# Connectors.net
KiCad netlist of a schematic drawn in Altium Designer
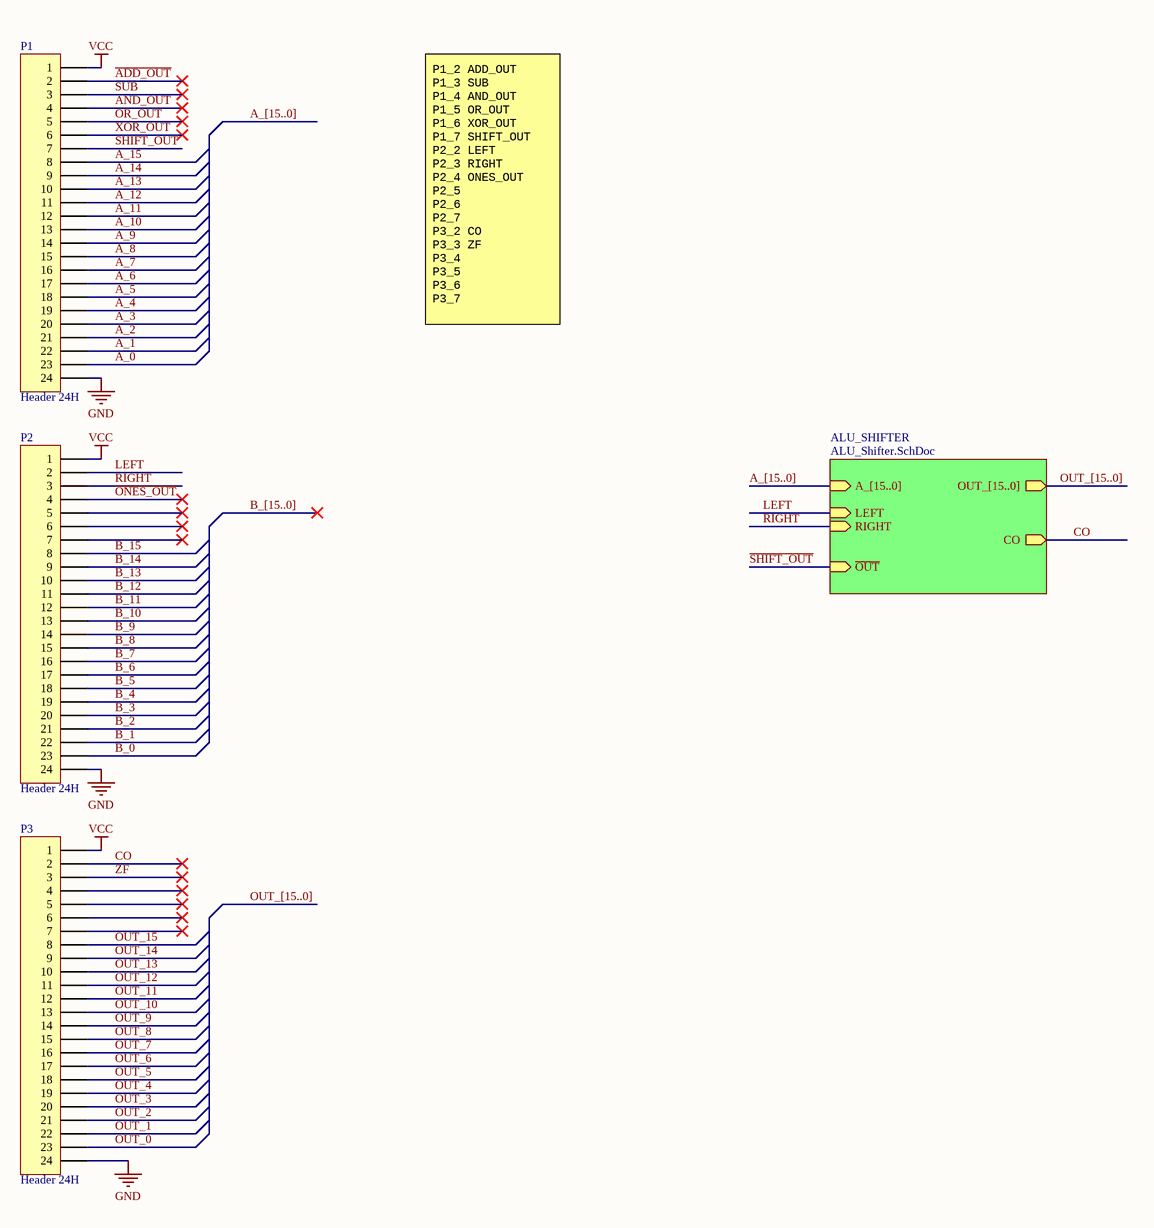
[diagram p0: Connectors.SchDoc]

(export (version "E")
  (design (tool "Eeschema 10.0.6"))
  (components
    (comp (ref "P1")
      (value "Header 24H")
      (footprint "HDR1X24H")
      (description "Header, 24-Pin, Right Angle")
      (fields (field (name "PUBLISHER") "Altium Limited"))
      (libsource (lib "Miscellaneous Connectors") (part "Header 24H"))
    )
    (comp (ref "P2")
      (value "Header 24H")
      (footprint "HDR1X24H")
      (description "Header, 24-Pin, Right Angle")
      (fields (field (name "PUBLISHER") "Altium Limited"))
      (libsource (lib "Miscellaneous Connectors") (part "Header 24H"))
    )
    (comp (ref "P3")
      (value "Header 24H")
      (footprint "HDR1X24H")
      (description "Header, 24-Pin, Right Angle")
      (fields (field (name "PUBLISHER") "Altium Limited"))
      (libsource (lib "Miscellaneous Connectors") (part "Header 24H"))
    )
  )
  (nets
    (net (code "1") (name "/A_0") (class "Default")
      (node (ref "P1") (pin "23") (pinfunction "23_23") (pintype "passive"))
    )
    (net (code "2") (name "/A_1") (class "Default")
      (node (ref "P1") (pin "22") (pinfunction "22_22") (pintype "passive"))
    )
    (net (code "3") (name "/A_2") (class "Default")
      (node (ref "P1") (pin "21") (pinfunction "21_21") (pintype "passive"))
    )
    (net (code "4") (name "/A_3") (class "Default")
      (node (ref "P1") (pin "20") (pinfunction "20_20") (pintype "passive"))
    )
    (net (code "5") (name "/A_4") (class "Default")
      (node (ref "P1") (pin "19") (pinfunction "19_19") (pintype "passive"))
    )
    (net (code "6") (name "/A_5") (class "Default")
      (node (ref "P1") (pin "18") (pinfunction "18_18") (pintype "passive"))
    )
    (net (code "7") (name "/A_6") (class "Default")
      (node (ref "P1") (pin "17") (pinfunction "17_17") (pintype "passive"))
    )
    (net (code "8") (name "/A_7") (class "Default")
      (node (ref "P1") (pin "16") (pinfunction "16_16") (pintype "passive"))
    )
    (net (code "9") (name "/A_8") (class "Default")
      (node (ref "P1") (pin "15") (pinfunction "15_15") (pintype "passive"))
    )
    (net (code "10") (name "/A_9") (class "Default")
      (node (ref "P1") (pin "14") (pinfunction "14_14") (pintype "passive"))
    )
    (net (code "11") (name "/A_10") (class "Default")
      (node (ref "P1") (pin "13") (pinfunction "13_13") (pintype "passive"))
    )
    (net (code "12") (name "/A_11") (class "Default")
      (node (ref "P1") (pin "12") (pinfunction "12_12") (pintype "passive"))
    )
    (net (code "13") (name "/A_12") (class "Default")
      (node (ref "P1") (pin "11") (pinfunction "11_11") (pintype "passive"))
    )
    (net (code "14") (name "/A_13") (class "Default")
      (node (ref "P1") (pin "10") (pinfunction "10_10") (pintype "passive"))
    )
    (net (code "15") (name "/A_14") (class "Default")
      (node (ref "P1") (pin "9") (pinfunction "9_9") (pintype "passive"))
    )
    (net (code "16") (name "/A_15") (class "Default")
      (node (ref "P1") (pin "8") (pinfunction "8_8") (pintype "passive"))
    )
    (net (code "18") (name "/B_0") (class "Default")
      (node (ref "P2") (pin "23") (pinfunction "23_23") (pintype "passive"))
    )
    (net (code "19") (name "/B_1") (class "Default")
      (node (ref "P2") (pin "22") (pinfunction "22_22") (pintype "passive"))
    )
    (net (code "20") (name "/B_2") (class "Default")
      (node (ref "P2") (pin "21") (pinfunction "21_21") (pintype "passive"))
    )
    (net (code "21") (name "/B_3") (class "Default")
      (node (ref "P2") (pin "20") (pinfunction "20_20") (pintype "passive"))
    )
    (net (code "22") (name "/B_4") (class "Default")
      (node (ref "P2") (pin "19") (pinfunction "19_19") (pintype "passive"))
    )
    (net (code "23") (name "/B_5") (class "Default")
      (node (ref "P2") (pin "18") (pinfunction "18_18") (pintype "passive"))
    )
    (net (code "24") (name "/B_6") (class "Default")
      (node (ref "P2") (pin "17") (pinfunction "17_17") (pintype "passive"))
    )
    (net (code "25") (name "/B_7") (class "Default")
      (node (ref "P2") (pin "16") (pinfunction "16_16") (pintype "passive"))
    )
    (net (code "26") (name "/B_8") (class "Default")
      (node (ref "P2") (pin "15") (pinfunction "15_15") (pintype "passive"))
    )
    (net (code "27") (name "/B_9") (class "Default")
      (node (ref "P2") (pin "14") (pinfunction "14_14") (pintype "passive"))
    )
    (net (code "28") (name "/B_10") (class "Default")
      (node (ref "P2") (pin "13") (pinfunction "13_13") (pintype "passive"))
    )
    (net (code "29") (name "/B_11") (class "Default")
      (node (ref "P2") (pin "12") (pinfunction "12_12") (pintype "passive"))
    )
    (net (code "30") (name "/B_12") (class "Default")
      (node (ref "P2") (pin "11") (pinfunction "11_11") (pintype "passive"))
    )
    (net (code "31") (name "/B_13") (class "Default")
      (node (ref "P2") (pin "10") (pinfunction "10_10") (pintype "passive"))
    )
    (net (code "32") (name "/B_14") (class "Default")
      (node (ref "P2") (pin "9") (pinfunction "9_9") (pintype "passive"))
    )
    (net (code "33") (name "/B_15") (class "Default")
      (node (ref "P2") (pin "8") (pinfunction "8_8") (pintype "passive"))
    )
    (net (code "35") (name "/CO") (class "Default")
      (node (ref "P3") (pin "2") (pinfunction "2_2") (pintype "passive"))
    )
    (net (code "36") (name "/LEFT") (class "Default")
      (node (ref "P2") (pin "2") (pinfunction "2_2") (pintype "passive"))
    )
    (net (code "37") (name "/OUT_0") (class "Default")
      (node (ref "P3") (pin "23") (pinfunction "23_23") (pintype "passive"))
    )
    (net (code "38") (name "/OUT_1") (class "Default")
      (node (ref "P3") (pin "22") (pinfunction "22_22") (pintype "passive"))
    )
    (net (code "39") (name "/OUT_2") (class "Default")
      (node (ref "P3") (pin "21") (pinfunction "21_21") (pintype "passive"))
    )
    (net (code "40") (name "/OUT_3") (class "Default")
      (node (ref "P3") (pin "20") (pinfunction "20_20") (pintype "passive"))
    )
    (net (code "41") (name "/OUT_4") (class "Default")
      (node (ref "P3") (pin "19") (pinfunction "19_19") (pintype "passive"))
    )
    (net (code "42") (name "/OUT_5") (class "Default")
      (node (ref "P3") (pin "18") (pinfunction "18_18") (pintype "passive"))
    )
    (net (code "43") (name "/OUT_6") (class "Default")
      (node (ref "P3") (pin "17") (pinfunction "17_17") (pintype "passive"))
    )
    (net (code "44") (name "/OUT_7") (class "Default")
      (node (ref "P3") (pin "16") (pinfunction "16_16") (pintype "passive"))
    )
    (net (code "45") (name "/OUT_8") (class "Default")
      (node (ref "P3") (pin "15") (pinfunction "15_15") (pintype "passive"))
    )
    (net (code "46") (name "/OUT_9") (class "Default")
      (node (ref "P3") (pin "14") (pinfunction "14_14") (pintype "passive"))
    )
    (net (code "47") (name "/OUT_10") (class "Default")
      (node (ref "P3") (pin "13") (pinfunction "13_13") (pintype "passive"))
    )
    (net (code "48") (name "/OUT_11") (class "Default")
      (node (ref "P3") (pin "12") (pinfunction "12_12") (pintype "passive"))
    )
    (net (code "49") (name "/OUT_12") (class "Default")
      (node (ref "P3") (pin "11") (pinfunction "11_11") (pintype "passive"))
    )
    (net (code "50") (name "/OUT_13") (class "Default")
      (node (ref "P3") (pin "10") (pinfunction "10_10") (pintype "passive"))
    )
    (net (code "51") (name "/OUT_14") (class "Default")
      (node (ref "P3") (pin "9") (pinfunction "9_9") (pintype "passive"))
    )
    (net (code "52") (name "/OUT_15") (class "Default")
      (node (ref "P3") (pin "8") (pinfunction "8_8") (pintype "passive"))
    )
    (net (code "54") (name "/RIGHT") (class "Default")
      (node (ref "P2") (pin "3") (pinfunction "3_3") (pintype "passive"))
    )
    (net (code "55") (name "/SUB") (class "Default")
      (node (ref "P1") (pin "3") (pinfunction "3_3") (pintype "passive+no_connect"))
    )
    (net (code "56") (name "/~{ADD_OUT}") (class "Default")
      (node (ref "P1") (pin "2") (pinfunction "2_2") (pintype "passive+no_connect"))
    )
    (net (code "57") (name "/~{AND_OUT}") (class "Default")
      (node (ref "P1") (pin "4") (pinfunction "4_4") (pintype "passive+no_connect"))
    )
    (net (code "58") (name "/~{ONES_OUT}") (class "Default")
      (node (ref "P2") (pin "4") (pinfunction "4_4") (pintype "passive+no_connect"))
    )
    (net (code "59") (name "/~{OR_OUT}") (class "Default")
      (node (ref "P1") (pin "5") (pinfunction "5_5") (pintype "passive+no_connect"))
    )
    (net (code "60") (name "/~{SHIFT_OUT}") (class "Default")
      (node (ref "P1") (pin "7") (pinfunction "7_7") (pintype "passive"))
    )
    (net (code "61") (name "/~{XOR_OUT}") (class "Default")
      (node (ref "P1") (pin "6") (pinfunction "6_6") (pintype "passive+no_connect"))
    )
    (net (code "62") (name "/~{ZF}") (class "Default")
      (node (ref "P3") (pin "3") (pinfunction "3_3") (pintype "passive+no_connect"))
    )
    (net (code "63") (name "GND") (class "Default")
      (node (ref "P1") (pin "24") (pinfunction "24_24") (pintype "passive"))
      (node (ref "P2") (pin "24") (pinfunction "24_24") (pintype "passive"))
      (node (ref "P3") (pin "24") (pinfunction "24_24") (pintype "passive"))
    )
    (net (code "64") (name "VCC") (class "Default")
      (node (ref "P1") (pin "1") (pinfunction "1_1") (pintype "passive"))
      (node (ref "P2") (pin "1") (pinfunction "1_1") (pintype "passive"))
      (node (ref "P3") (pin "1") (pinfunction "1_1") (pintype "passive"))
    )
    (net (code "65") (name "unconnected-(P2-Pad5)") (class "Default")
      (node (ref "P2") (pin "5") (pinfunction "5_5") (pintype "passive+no_connect"))
    )
    (net (code "66") (name "unconnected-(P2-Pad6)") (class "Default")
      (node (ref "P2") (pin "6") (pinfunction "6_6") (pintype "passive+no_connect"))
    )
    (net (code "67") (name "unconnected-(P2-Pad7)") (class "Default")
      (node (ref "P2") (pin "7") (pinfunction "7_7") (pintype "passive+no_connect"))
    )
    (net (code "68") (name "unconnected-(P3-Pad4)") (class "Default")
      (node (ref "P3") (pin "4") (pinfunction "4_4") (pintype "passive+no_connect"))
    )
    (net (code "69") (name "unconnected-(P3-Pad5)") (class "Default")
      (node (ref "P3") (pin "5") (pinfunction "5_5") (pintype "passive+no_connect"))
    )
    (net (code "70") (name "unconnected-(P3-Pad6)") (class "Default")
      (node (ref "P3") (pin "6") (pinfunction "6_6") (pintype "passive+no_connect"))
    )
    (net (code "71") (name "unconnected-(P3-Pad7)") (class "Default")
      (node (ref "P3") (pin "7") (pinfunction "7_7") (pintype "passive+no_connect"))
    )
  )
)
